# OV5640.net
KiCad netlist of a schematic drawn in EAGLE
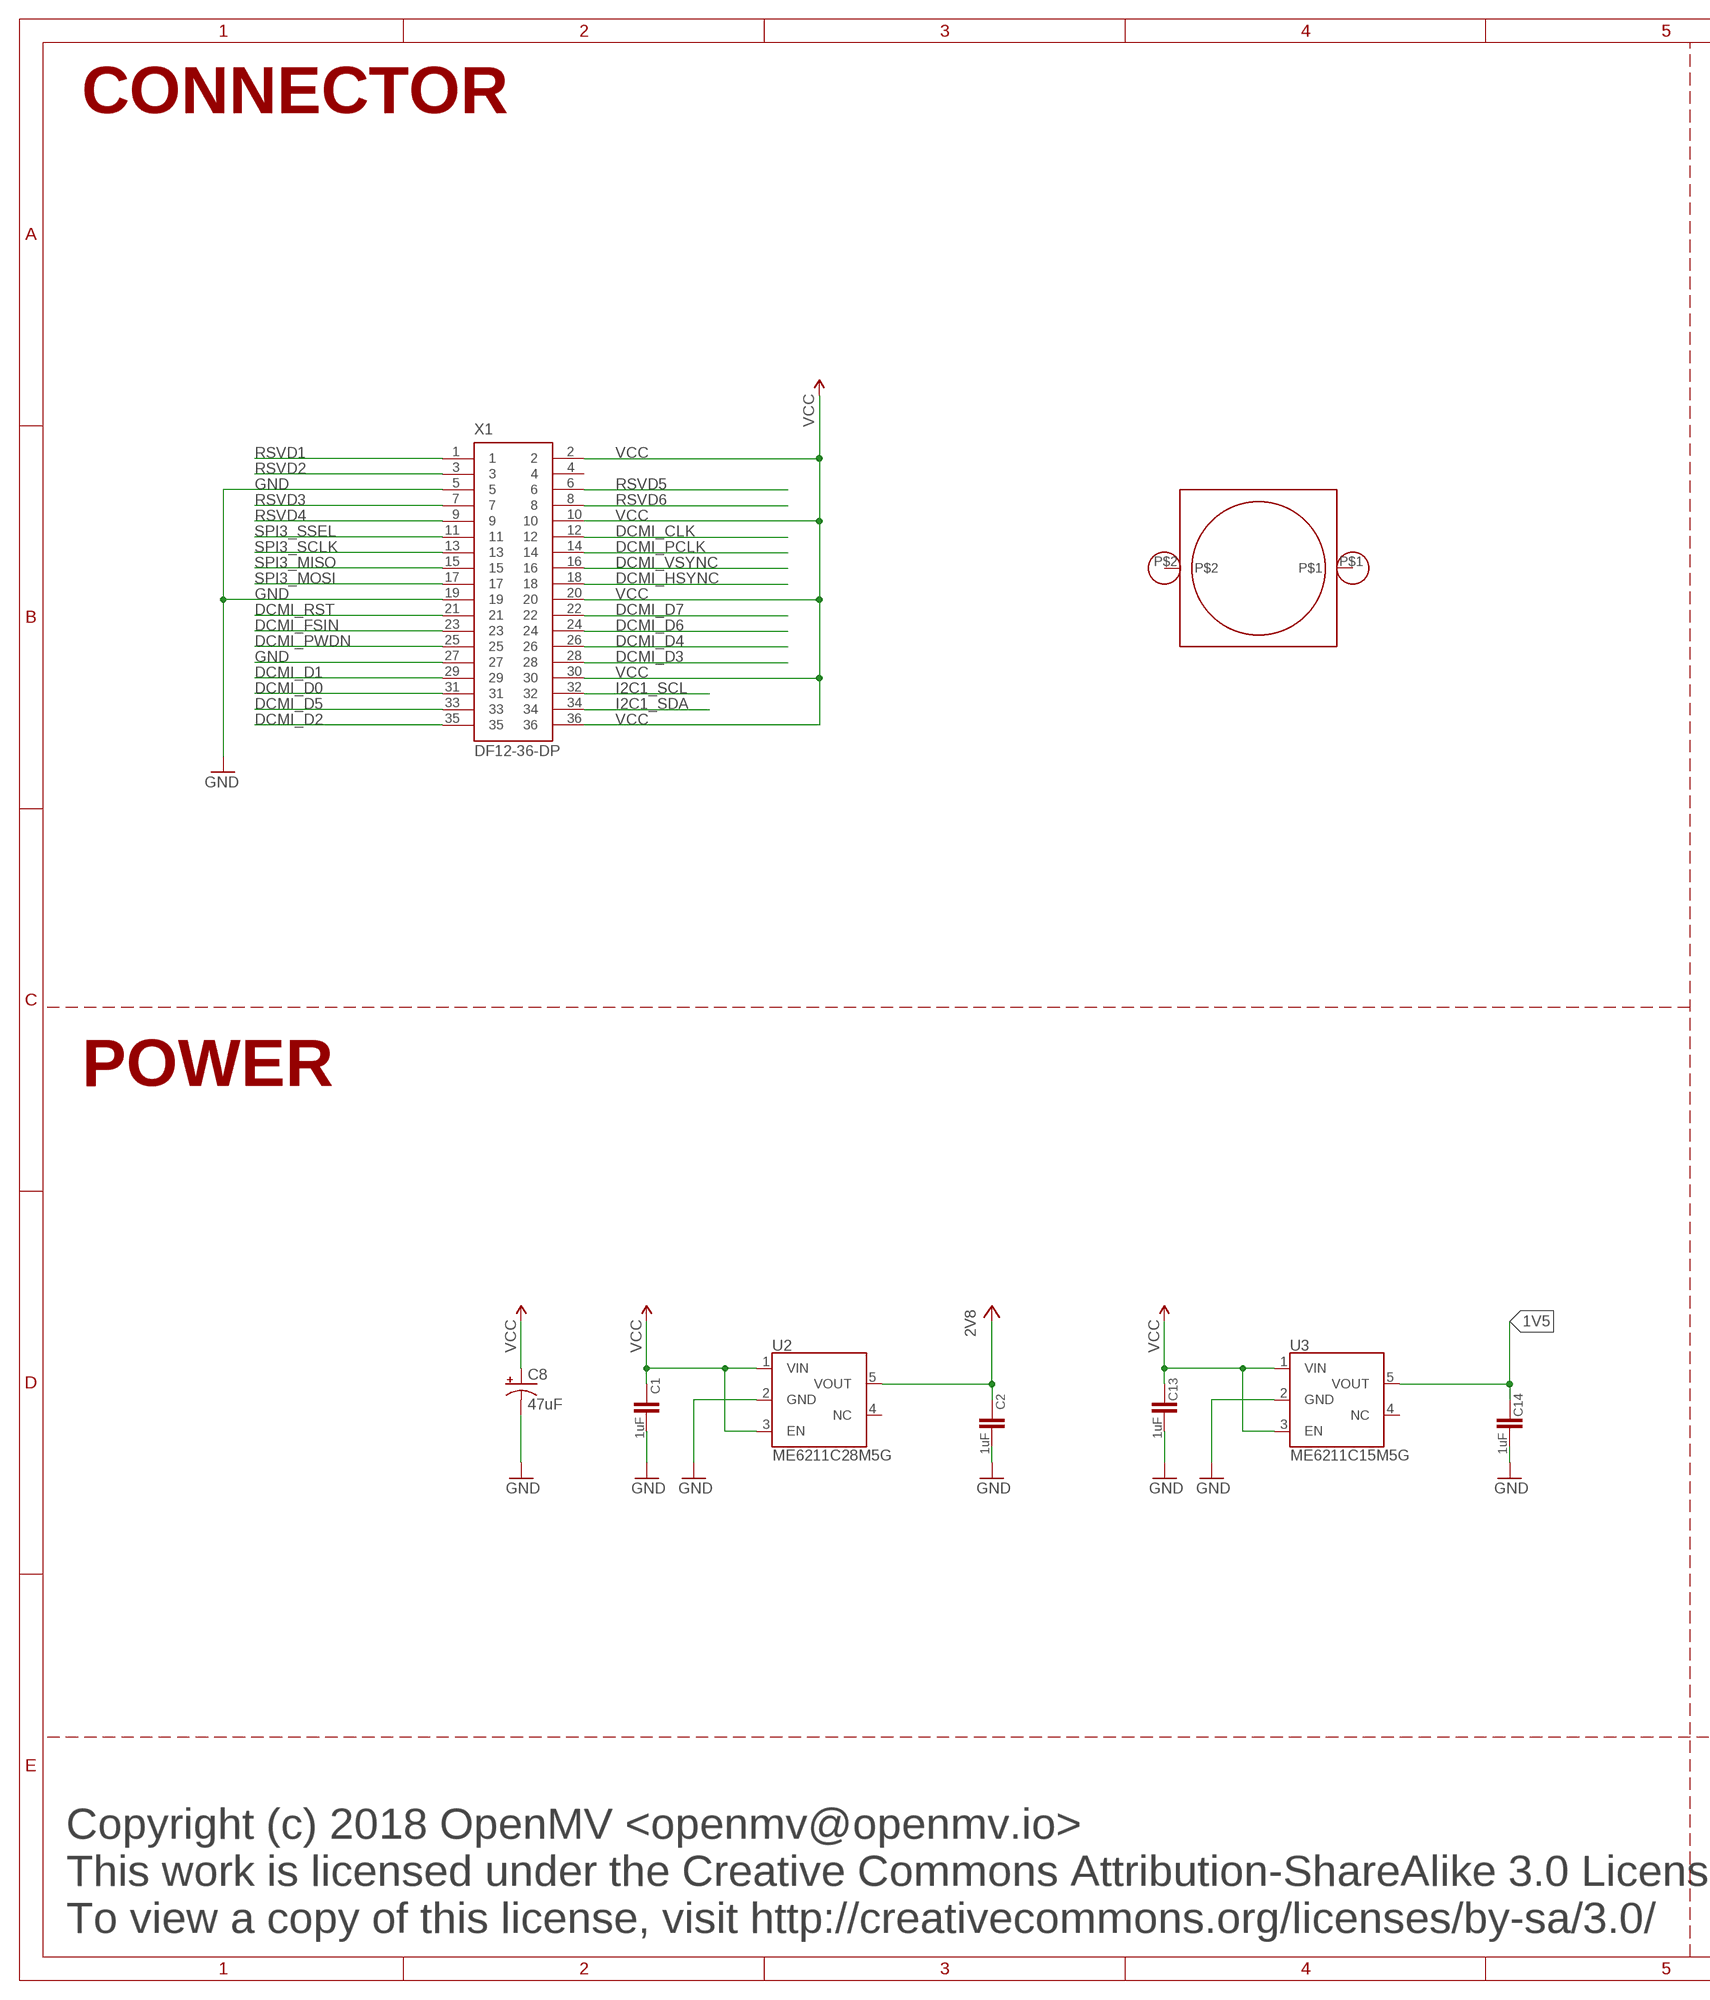
[diagram p0: schematic, sheet 1, part 1 of 2]
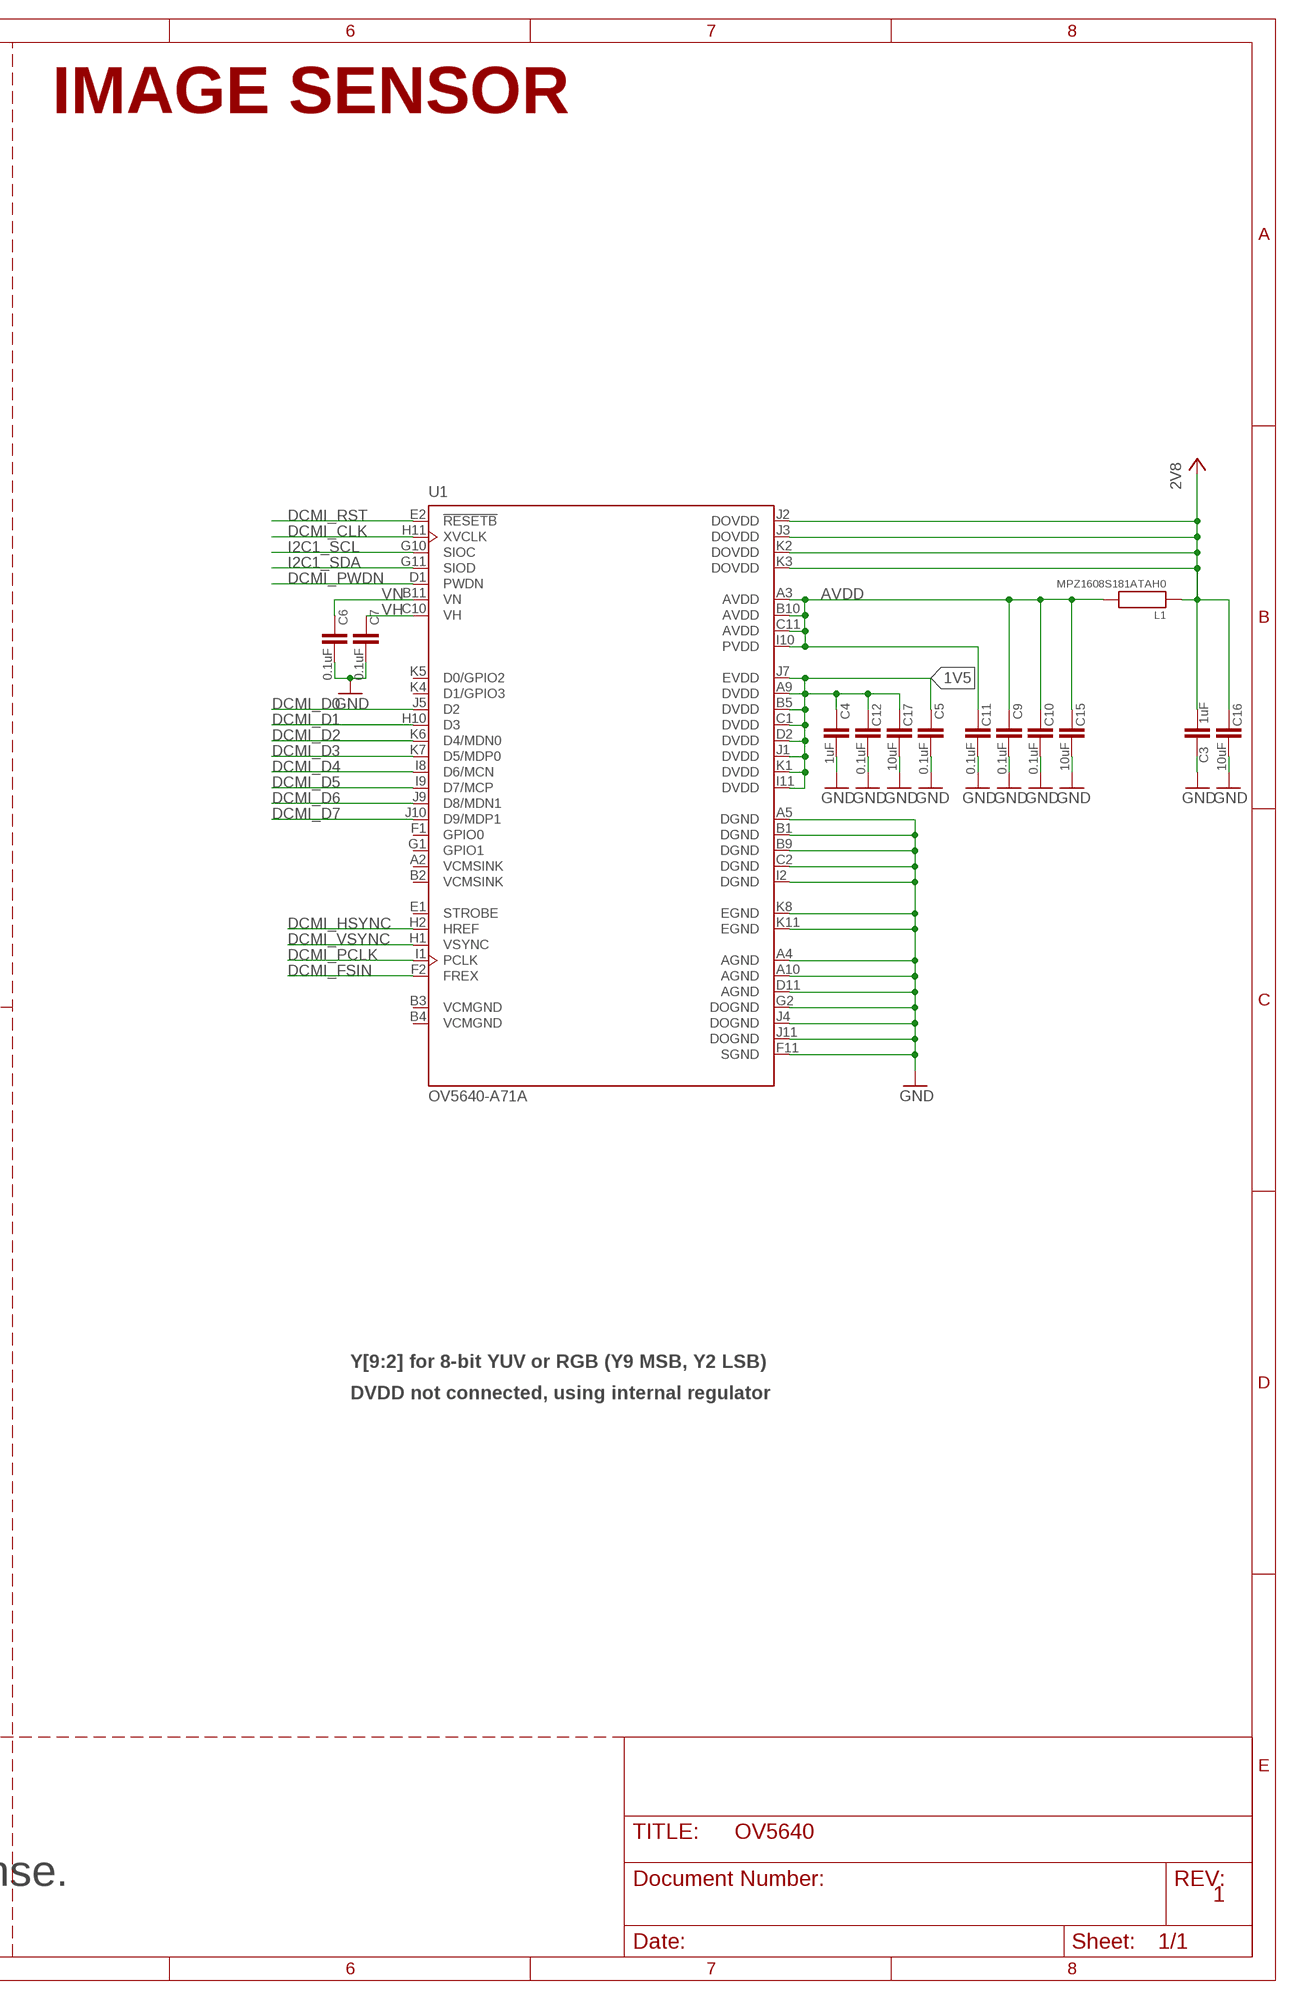
[diagram p1: schematic, sheet 1, part 2 of 2]

(export (version "E")
  (design (tool "Eeschema 10.0.6"))
  (components
    (comp (ref "C1")
      (value "1uF")
      (footprint "eagle-import:0402-CAP")
      (libsource (lib "eagle-import") (part "CAP0402-CAP"))
    )
    (comp (ref "C2")
      (value "1uF")
      (footprint "eagle-import:0402-CAP")
      (libsource (lib "eagle-import") (part "CAP0402-CAP"))
    )
    (comp (ref "C3")
      (value "1uF")
      (footprint "eagle-import:0402-CAP")
      (libsource (lib "eagle-import") (part "CAP0402-CAP"))
    )
    (comp (ref "C4")
      (value "1uF")
      (footprint "eagle-import:0402-CAP")
      (libsource (lib "eagle-import") (part "CAP0402-CAP"))
    )
    (comp (ref "C5")
      (value "0.1uF")
      (footprint "eagle-import:0402-CAP")
      (libsource (lib "eagle-import") (part "CAP0402-CAP"))
    )
    (comp (ref "C6")
      (value "0.1uF")
      (footprint "eagle-import:0402-CAP")
      (libsource (lib "eagle-import") (part "CAP0402-CAP"))
    )
    (comp (ref "C7")
      (value "0.1uF")
      (footprint "eagle-import:0402-CAP")
      (libsource (lib "eagle-import") (part "CAP0402-CAP"))
    )
    (comp (ref "C8")
      (value "47uF")
      (footprint "eagle-import:EIA3216")
      (libsource (lib "eagle-import") (part "CAP_POL1206"))
    )
    (comp (ref "C9")
      (value "0.1uF")
      (footprint "eagle-import:0402-CAP")
      (libsource (lib "eagle-import") (part "CAP0402-CAP"))
    )
    (comp (ref "C10")
      (value "0.1uF")
      (footprint "eagle-import:0402-CAP")
      (libsource (lib "eagle-import") (part "CAP0402-CAP"))
    )
    (comp (ref "C11")
      (value "0.1uF")
      (footprint "eagle-import:0402-CAP")
      (libsource (lib "eagle-import") (part "CAP0402-CAP"))
    )
    (comp (ref "C12")
      (value "0.1uF")
      (footprint "eagle-import:0402-CAP")
      (libsource (lib "eagle-import") (part "CAP0402-CAP"))
    )
    (comp (ref "C13")
      (value "1uF")
      (footprint "eagle-import:0402-CAP")
      (libsource (lib "eagle-import") (part "CAP0402-CAP"))
    )
    (comp (ref "C14")
      (value "1uF")
      (footprint "eagle-import:0402-CAP")
      (libsource (lib "eagle-import") (part "CAP0402-CAP"))
    )
    (comp (ref "C15")
      (value "10uF")
      (footprint "eagle-import:0402-CAP")
      (libsource (lib "eagle-import") (part "CAP0402-CAP"))
    )
    (comp (ref "C16")
      (value "10uF")
      (footprint "eagle-import:0402-CAP")
      (libsource (lib "eagle-import") (part "CAP0402-CAP"))
    )
    (comp (ref "C17")
      (value "10uF")
      (footprint "eagle-import:0402-CAP")
      (libsource (lib "eagle-import") (part "CAP0402-CAP"))
    )
    (comp (ref "L1")
      (value "MPZ1608S181ATAH0")
      (footprint "eagle-import:0402-CAP")
      (libsource (lib "eagle-import") (part "BEAD"))
    )
    (comp (ref "LM1")
      (value "LENSMOUNT20MM")
      (footprint "eagle-import:LENSMOUNT-20MM")
      (libsource (lib "eagle-import") (part "LENSMOUNT20MM"))
    )
    (comp (ref "U1")
      (value "OV5640-A71A")
      (footprint "eagle-import:BGA71C50P11X11_598X584X81")
      (fields (field (name "MF") "Omron"))
      (libsource (lib "eagle-import") (part "OV5640-A71A"))
    )
    (comp (ref "U2")
      (value "ME6211C28M5G")
      (footprint "eagle-import:SOT23-5")
      (libsource (lib "eagle-import") (part "ADP150TSOT-5"))
    )
    (comp (ref "U3")
      (value "ME6211C15M5G")
      (footprint "eagle-import:SOT23-5")
      (libsource (lib "eagle-import") (part "ADP150TSOT-5"))
    )
    (comp (ref "X1")
      (value "DF12-36-DP")
      (footprint "eagle-import:DF12-36-DP")
      (libsource (lib "eagle-import") (part "DF12-36-DP"))
    )
  )
  (nets
    (net (code "1") (name "/AVDD") (class "Default")
      (node (ref "C10") (pin "2") (pinfunction "2_2") (pintype "passive"))
      (node (ref "C11") (pin "2") (pinfunction "2_2") (pintype "passive"))
      (node (ref "C15") (pin "2") (pinfunction "2_2") (pintype "passive"))
      (node (ref "C9") (pin "2") (pinfunction "2_2") (pintype "passive"))
      (node (ref "L1") (pin "2") (pinfunction "2_2") (pintype "passive"))
      (node (ref "U1") (pin "A3") (pinfunction "AVDD_A3") (pintype "power_in"))
      (node (ref "U1") (pin "B10") (pinfunction "AVDD_B10") (pintype "power_in"))
      (node (ref "U1") (pin "C11") (pinfunction "AVDD_C11") (pintype "power_in"))
      (node (ref "U1") (pin "I10") (pinfunction "PVDD_I10") (pintype "power_in"))
    )
    (net (code "2") (name "/DCMI_CLK") (class "Default")
      (node (ref "U1") (pin "H11") (pinfunction "XVCLK_H11") (pintype "input"))
      (node (ref "X1") (pin "12") (pinfunction "12_12") (pintype "bidirectional"))
    )
    (net (code "3") (name "/DCMI_D0") (class "Default")
      (node (ref "U1") (pin "J5") (pinfunction "D2_J5") (pintype "bidirectional"))
      (node (ref "X1") (pin "31") (pinfunction "31_31") (pintype "bidirectional"))
    )
    (net (code "4") (name "/DCMI_D1") (class "Default")
      (node (ref "U1") (pin "H10") (pinfunction "D3_H10") (pintype "bidirectional"))
      (node (ref "X1") (pin "29") (pinfunction "29_29") (pintype "bidirectional"))
    )
    (net (code "5") (name "/DCMI_D2") (class "Default")
      (node (ref "U1") (pin "K6") (pinfunction "D4/MDN0_K6") (pintype "bidirectional"))
      (node (ref "X1") (pin "35") (pinfunction "35_35") (pintype "bidirectional"))
    )
    (net (code "6") (name "/DCMI_D3") (class "Default")
      (node (ref "U1") (pin "K7") (pinfunction "D5/MDP0_K7") (pintype "bidirectional"))
      (node (ref "X1") (pin "28") (pinfunction "28_28") (pintype "bidirectional"))
    )
    (net (code "7") (name "/DCMI_D4") (class "Default")
      (node (ref "U1") (pin "I8") (pinfunction "D6/MCN_I8") (pintype "bidirectional"))
      (node (ref "X1") (pin "26") (pinfunction "26_26") (pintype "bidirectional"))
    )
    (net (code "8") (name "/DCMI_D5") (class "Default")
      (node (ref "U1") (pin "I9") (pinfunction "D7/MCP_I9") (pintype "bidirectional"))
      (node (ref "X1") (pin "33") (pinfunction "33_33") (pintype "bidirectional"))
    )
    (net (code "9") (name "/DCMI_D6") (class "Default")
      (node (ref "U1") (pin "J9") (pinfunction "D8/MDN1_J9") (pintype "bidirectional"))
      (node (ref "X1") (pin "24") (pinfunction "24_24") (pintype "bidirectional"))
    )
    (net (code "10") (name "/DCMI_D7") (class "Default")
      (node (ref "U1") (pin "J10") (pinfunction "D9/MDP1_J10") (pintype "bidirectional"))
      (node (ref "X1") (pin "22") (pinfunction "22_22") (pintype "bidirectional"))
    )
    (net (code "11") (name "/DCMI_FSIN") (class "Default")
      (node (ref "U1") (pin "F2") (pinfunction "FREX_F2") (pintype "bidirectional"))
      (node (ref "X1") (pin "23") (pinfunction "23_23") (pintype "bidirectional"))
    )
    (net (code "12") (name "/DCMI_HSYNC") (class "Default")
      (node (ref "U1") (pin "H2") (pinfunction "HREF_H2") (pintype "bidirectional"))
      (node (ref "X1") (pin "18") (pinfunction "18_18") (pintype "bidirectional"))
    )
    (net (code "13") (name "/DCMI_PCLK") (class "Default")
      (node (ref "U1") (pin "I1") (pinfunction "PCLK_I1") (pintype "bidirectional"))
      (node (ref "X1") (pin "14") (pinfunction "14_14") (pintype "bidirectional"))
    )
    (net (code "14") (name "/DCMI_PWDN") (class "Default")
      (node (ref "U1") (pin "D1") (pinfunction "PWDN_D1") (pintype "input"))
      (node (ref "X1") (pin "25") (pinfunction "25_25") (pintype "bidirectional"))
    )
    (net (code "15") (name "/DCMI_RST") (class "Default")
      (node (ref "U1") (pin "E2") (pinfunction "~{RESETB}_E2") (pintype "input"))
      (node (ref "X1") (pin "21") (pinfunction "21_21") (pintype "bidirectional"))
    )
    (net (code "16") (name "/DCMI_VSYNC") (class "Default")
      (node (ref "U1") (pin "H1") (pinfunction "VSYNC_H1") (pintype "bidirectional"))
      (node (ref "X1") (pin "16") (pinfunction "16_16") (pintype "bidirectional"))
    )
    (net (code "17") (name "/I2C1_SCL") (class "Default")
      (node (ref "U1") (pin "G10") (pinfunction "SIOC_G10") (pintype "input"))
      (node (ref "X1") (pin "32") (pinfunction "32_32") (pintype "bidirectional"))
    )
    (net (code "18") (name "/I2C1_SDA") (class "Default")
      (node (ref "U1") (pin "G11") (pinfunction "SIOD_G11") (pintype "bidirectional"))
      (node (ref "X1") (pin "34") (pinfunction "34_34") (pintype "bidirectional"))
    )
    (net (code "19") (name "/P$1") (class "Default")
      (node (ref "LM1") (pin "P$1") (pinfunction "P$1_P$1") (pintype "power_in"))
    )
    (net (code "20") (name "/P$2") (class "Default")
      (node (ref "LM1") (pin "P$2") (pinfunction "P$2_P$2") (pintype "power_in"))
    )
    (net (code "21") (name "/RSVD1") (class "Default")
      (node (ref "X1") (pin "1") (pinfunction "1_1") (pintype "bidirectional"))
    )
    (net (code "22") (name "/RSVD2") (class "Default")
      (node (ref "X1") (pin "3") (pinfunction "3_3") (pintype "bidirectional"))
    )
    (net (code "23") (name "/RSVD3") (class "Default")
      (node (ref "X1") (pin "7") (pinfunction "7_7") (pintype "bidirectional"))
    )
    (net (code "24") (name "/RSVD4") (class "Default")
      (node (ref "X1") (pin "9") (pinfunction "9_9") (pintype "bidirectional"))
    )
    (net (code "25") (name "/RSVD5") (class "Default")
      (node (ref "X1") (pin "6") (pinfunction "6_6") (pintype "bidirectional"))
    )
    (net (code "26") (name "/RSVD6") (class "Default")
      (node (ref "X1") (pin "8") (pinfunction "8_8") (pintype "bidirectional"))
    )
    (net (code "27") (name "/SPI3_MISO") (class "Default")
      (node (ref "X1") (pin "15") (pinfunction "15_15") (pintype "bidirectional"))
    )
    (net (code "28") (name "/SPI3_MOSI") (class "Default")
      (node (ref "X1") (pin "17") (pinfunction "17_17") (pintype "bidirectional"))
    )
    (net (code "29") (name "/SPI3_SCLK") (class "Default")
      (node (ref "X1") (pin "13") (pinfunction "13_13") (pintype "bidirectional"))
    )
    (net (code "30") (name "/SPI3_SSEL") (class "Default")
      (node (ref "X1") (pin "11") (pinfunction "11_11") (pintype "bidirectional"))
    )
    (net (code "31") (name "/VH") (class "Default")
      (node (ref "C7") (pin "2") (pinfunction "2_2") (pintype "passive"))
      (node (ref "U1") (pin "C10") (pinfunction "VH_C10") (pintype "input"))
    )
    (net (code "32") (name "/VN") (class "Default")
      (node (ref "C6") (pin "2") (pinfunction "2_2") (pintype "passive"))
      (node (ref "U1") (pin "B11") (pinfunction "VN_B11") (pintype "input"))
    )
    (net (code "33") (name "1V5") (class "Default")
      (node (ref "C12") (pin "2") (pinfunction "2_2") (pintype "passive"))
      (node (ref "C14") (pin "2") (pinfunction "2_2") (pintype "passive"))
      (node (ref "C17") (pin "2") (pinfunction "2_2") (pintype "passive"))
      (node (ref "C4") (pin "2") (pinfunction "2_2") (pintype "passive"))
      (node (ref "C5") (pin "2") (pinfunction "2_2") (pintype "passive"))
      (node (ref "U1") (pin "A9") (pinfunction "DVDD_A9") (pintype "power_in"))
      (node (ref "U1") (pin "B5") (pinfunction "DVDD_B5") (pintype "power_in"))
      (node (ref "U1") (pin "C1") (pinfunction "DVDD_C1") (pintype "power_in"))
      (node (ref "U1") (pin "D2") (pinfunction "DVDD_D2") (pintype "power_in"))
      (node (ref "U1") (pin "I11") (pinfunction "DVDD_I11") (pintype "power_in"))
      (node (ref "U1") (pin "J1") (pinfunction "DVDD_J1") (pintype "power_in"))
      (node (ref "U1") (pin "J7") (pinfunction "EVDD_J7") (pintype "power_in"))
      (node (ref "U1") (pin "K1") (pinfunction "DVDD_K1") (pintype "power_in"))
      (node (ref "U3") (pin "5") (pinfunction "VOUT_5") (pintype "power_in"))
    )
    (net (code "34") (name "2V8") (class "Default")
      (node (ref "C16") (pin "2") (pinfunction "2_2") (pintype "passive"))
      (node (ref "C2") (pin "2") (pinfunction "2_2") (pintype "passive"))
      (node (ref "C3") (pin "1") (pinfunction "1_1") (pintype "passive"))
      (node (ref "L1") (pin "1") (pinfunction "1_1") (pintype "passive"))
      (node (ref "U1") (pin "J2") (pinfunction "DOVDD_J2") (pintype "power_in"))
      (node (ref "U1") (pin "J3") (pinfunction "DOVDD_J3") (pintype "power_in"))
      (node (ref "U1") (pin "K2") (pinfunction "DOVDD_K2") (pintype "power_in"))
      (node (ref "U1") (pin "K3") (pinfunction "DOVDD_K3") (pintype "power_in"))
      (node (ref "U2") (pin "5") (pinfunction "VOUT_5") (pintype "power_in"))
    )
    (net (code "35") (name "GND") (class "Default")
      (node (ref "C1") (pin "1") (pinfunction "1_1") (pintype "passive"))
      (node (ref "C10") (pin "1") (pinfunction "1_1") (pintype "passive"))
      (node (ref "C11") (pin "1") (pinfunction "1_1") (pintype "passive"))
      (node (ref "C12") (pin "1") (pinfunction "1_1") (pintype "passive"))
      (node (ref "C13") (pin "1") (pinfunction "1_1") (pintype "passive"))
      (node (ref "C14") (pin "1") (pinfunction "1_1") (pintype "passive"))
      (node (ref "C15") (pin "1") (pinfunction "1_1") (pintype "passive"))
      (node (ref "C16") (pin "1") (pinfunction "1_1") (pintype "passive"))
      (node (ref "C17") (pin "1") (pinfunction "1_1") (pintype "passive"))
      (node (ref "C2") (pin "1") (pinfunction "1_1") (pintype "passive"))
      (node (ref "C3") (pin "2") (pinfunction "2_2") (pintype "passive"))
      (node (ref "C4") (pin "1") (pinfunction "1_1") (pintype "passive"))
      (node (ref "C5") (pin "1") (pinfunction "1_1") (pintype "passive"))
      (node (ref "C6") (pin "1") (pinfunction "1_1") (pintype "passive"))
      (node (ref "C7") (pin "1") (pinfunction "1_1") (pintype "passive"))
      (node (ref "C8") (pin "C") (pinfunction "-_C") (pintype "passive"))
      (node (ref "C9") (pin "1") (pinfunction "1_1") (pintype "passive"))
      (node (ref "U1") (pin "A10") (pinfunction "AGND_A10") (pintype "power_in"))
      (node (ref "U1") (pin "A4") (pinfunction "AGND_A4") (pintype "power_in"))
      (node (ref "U1") (pin "A5") (pinfunction "DGND_A5") (pintype "power_in"))
      (node (ref "U1") (pin "B1") (pinfunction "DGND_B1") (pintype "power_in"))
      (node (ref "U1") (pin "B9") (pinfunction "DGND_B9") (pintype "power_in"))
      (node (ref "U1") (pin "C2") (pinfunction "DGND_C2") (pintype "power_in"))
      (node (ref "U1") (pin "D11") (pinfunction "AGND_D11") (pintype "power_in"))
      (node (ref "U1") (pin "F11") (pinfunction "SGND_F11") (pintype "power_in"))
      (node (ref "U1") (pin "G2") (pinfunction "DOGND_G2") (pintype "power_in"))
      (node (ref "U1") (pin "I2") (pinfunction "DGND_I2") (pintype "power_in"))
      (node (ref "U1") (pin "J11") (pinfunction "DOGND_J11") (pintype "power_in"))
      (node (ref "U1") (pin "J4") (pinfunction "DOGND_J4") (pintype "power_in"))
      (node (ref "U1") (pin "K11") (pinfunction "EGND_K11") (pintype "power_in"))
      (node (ref "U1") (pin "K8") (pinfunction "EGND_K8") (pintype "power_in"))
      (node (ref "U2") (pin "2") (pinfunction "GND_2") (pintype "power_in"))
      (node (ref "U3") (pin "2") (pinfunction "GND_2") (pintype "power_in"))
      (node (ref "X1") (pin "19") (pinfunction "19_19") (pintype "bidirectional"))
      (node (ref "X1") (pin "27") (pinfunction "27_27") (pintype "bidirectional"))
      (node (ref "X1") (pin "5") (pinfunction "5_5") (pintype "bidirectional"))
    )
    (net (code "36") (name "VCC") (class "Default")
      (node (ref "C1") (pin "2") (pinfunction "2_2") (pintype "passive"))
      (node (ref "C13") (pin "2") (pinfunction "2_2") (pintype "passive"))
      (node (ref "C8") (pin "A") (pinfunction "+_A") (pintype "passive"))
      (node (ref "U2") (pin "1") (pinfunction "VIN_1") (pintype "power_in"))
      (node (ref "U2") (pin "3") (pinfunction "EN_3") (pintype "bidirectional"))
      (node (ref "U3") (pin "1") (pinfunction "VIN_1") (pintype "power_in"))
      (node (ref "U3") (pin "3") (pinfunction "EN_3") (pintype "bidirectional"))
      (node (ref "X1") (pin "10") (pinfunction "10_10") (pintype "bidirectional"))
      (node (ref "X1") (pin "2") (pinfunction "2_2") (pintype "bidirectional"))
      (node (ref "X1") (pin "20") (pinfunction "20_20") (pintype "bidirectional"))
      (node (ref "X1") (pin "30") (pinfunction "30_30") (pintype "bidirectional"))
      (node (ref "X1") (pin "36") (pinfunction "36_36") (pintype "bidirectional"))
    )
    (net (code "37") (name "unconnected-(U1-D0{slash}GPIO2-PadK5)") (class "Default")
      (node (ref "U1") (pin "K5") (pinfunction "D0/GPIO2_K5") (pintype "bidirectional"))
    )
    (net (code "38") (name "unconnected-(U1-D1{slash}GPIO3-PadK4)") (class "Default")
      (node (ref "U1") (pin "K4") (pinfunction "D1/GPIO3_K4") (pintype "bidirectional"))
    )
    (net (code "39") (name "unconnected-(U1-GPIO0-PadF1)") (class "Default")
      (node (ref "U1") (pin "F1") (pinfunction "GPIO0_F1") (pintype "bidirectional"))
    )
    (net (code "40") (name "unconnected-(U1-GPIO1-PadG1)") (class "Default")
      (node (ref "U1") (pin "G1") (pinfunction "GPIO1_G1") (pintype "bidirectional"))
    )
    (net (code "41") (name "unconnected-(U1-STROBE-PadE1)") (class "Default")
      (node (ref "U1") (pin "E1") (pinfunction "STROBE_E1") (pintype "bidirectional"))
    )
    (net (code "42") (name "unconnected-(U1-VCMGND-PadB3)") (class "Default")
      (node (ref "U1") (pin "B3") (pinfunction "VCMGND_B3") (pintype "bidirectional"))
    )
    (net (code "43") (name "unconnected-(U1-VCMGND-PadB4)") (class "Default")
      (node (ref "U1") (pin "B4") (pinfunction "VCMGND_B4") (pintype "bidirectional"))
    )
    (net (code "44") (name "unconnected-(U1-VCMSINK-PadA2)") (class "Default")
      (node (ref "U1") (pin "A2") (pinfunction "VCMSINK_A2") (pintype "bidirectional"))
    )
    (net (code "45") (name "unconnected-(U1-VCMSINK-PadB2)") (class "Default")
      (node (ref "U1") (pin "B2") (pinfunction "VCMSINK_B2") (pintype "bidirectional"))
    )
    (net (code "46") (name "unconnected-(U2-NC-Pad4)") (class "Default")
      (node (ref "U2") (pin "4") (pinfunction "NC_4") (pintype "bidirectional"))
    )
    (net (code "47") (name "unconnected-(U3-NC-Pad4)") (class "Default")
      (node (ref "U3") (pin "4") (pinfunction "NC_4") (pintype "bidirectional"))
    )
    (net (code "48") (name "unconnected-(X1-Pad4)") (class "Default")
      (node (ref "X1") (pin "4") (pinfunction "4_4") (pintype "bidirectional"))
    )
  )
)
